# SM2200.net
KiCad netlist of a schematic drawn in Altium Designer
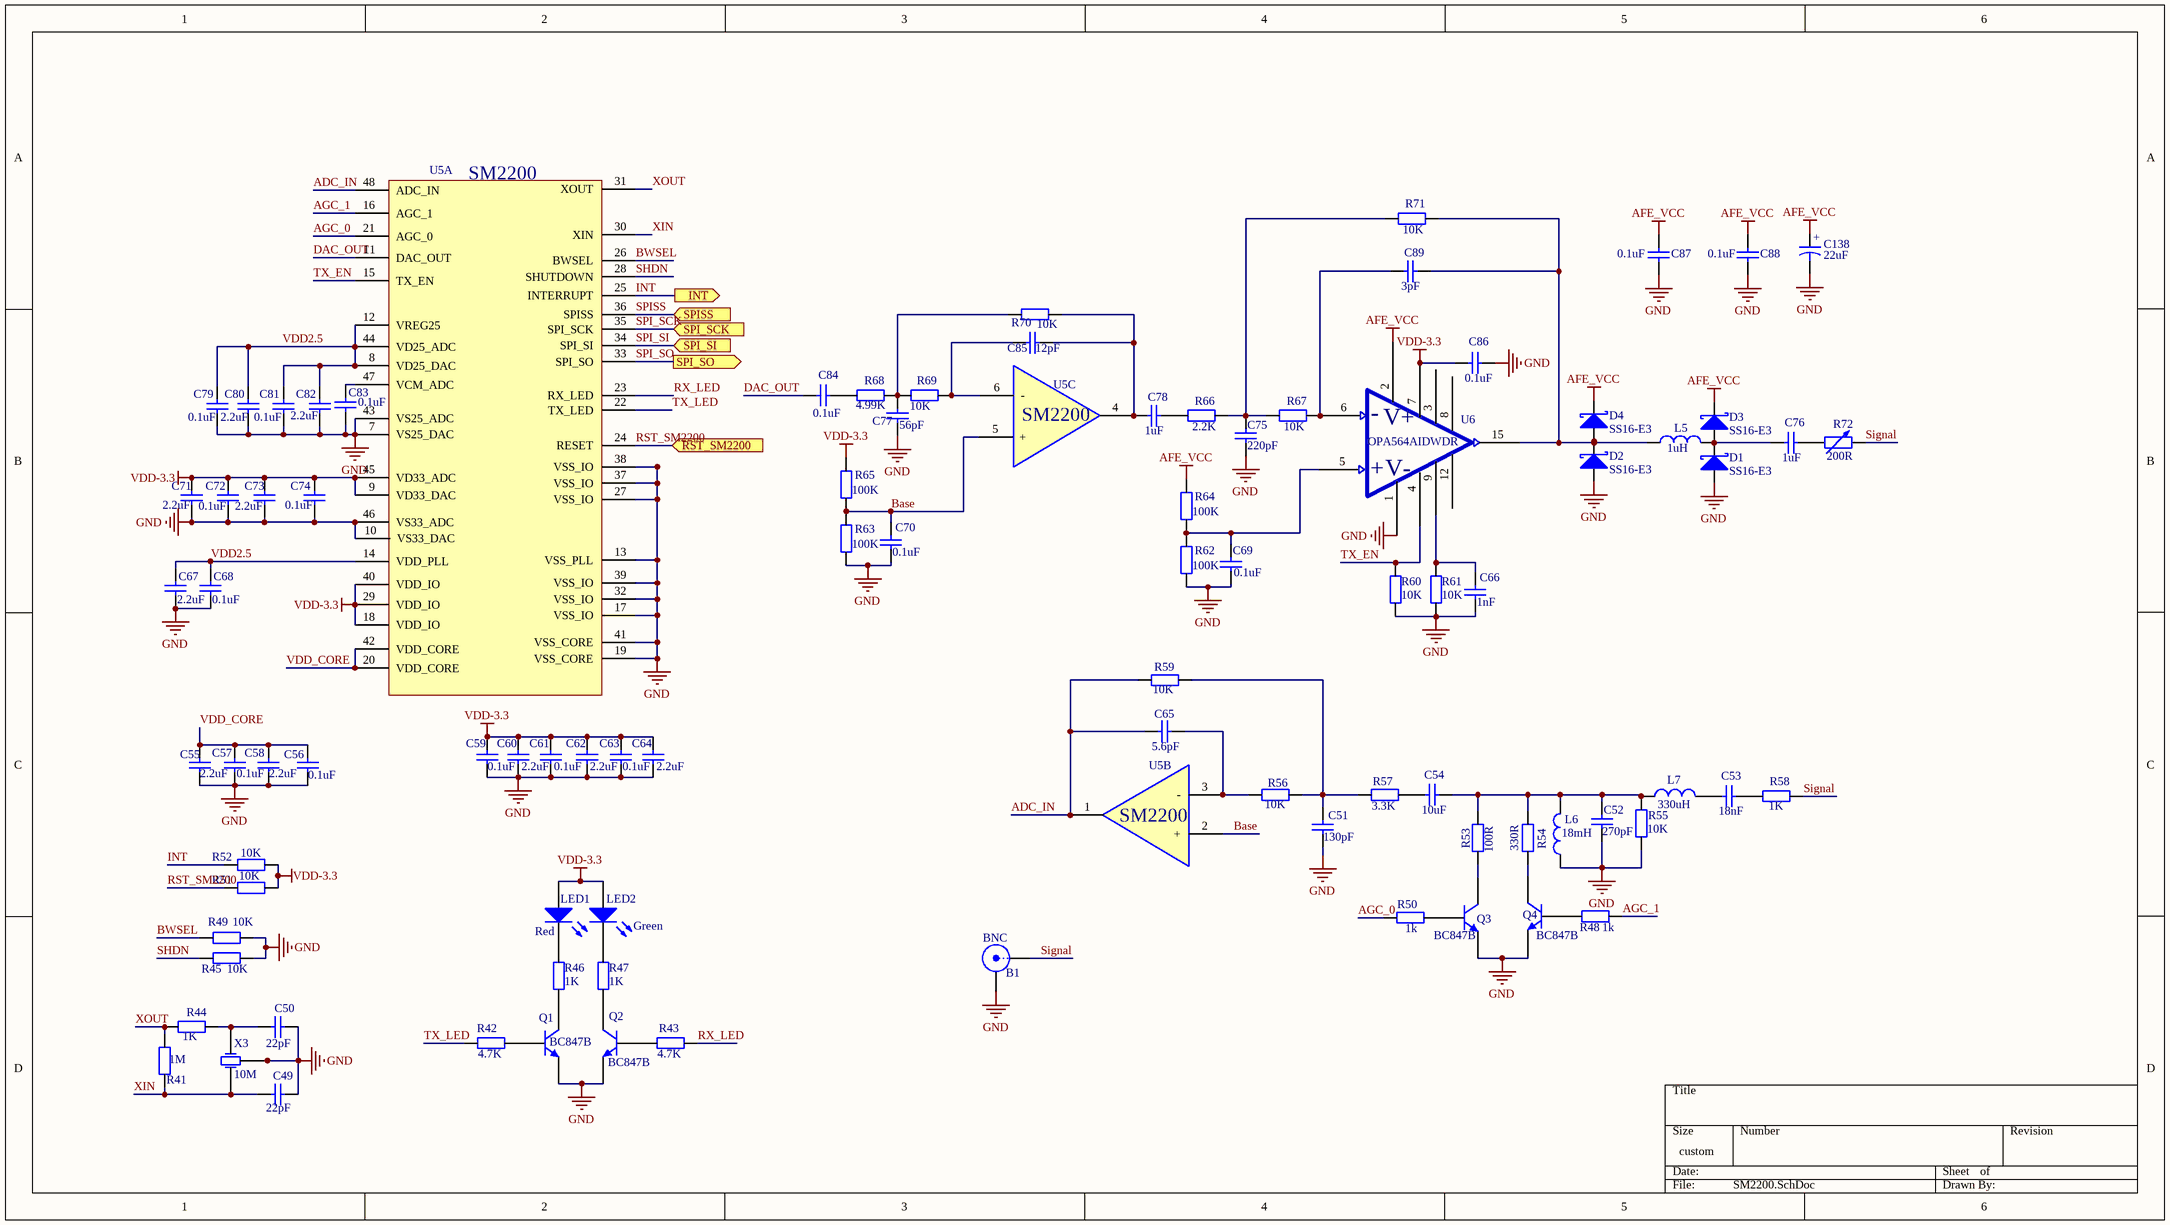
[diagram p0: SM2200.SchDoc]

(export (version "E")
  (design (tool "Eeschema 10.0.6"))
  (components
    (comp (ref "B1")
      (value "BNC")
      (footprint "BNC")
      (fields (field (name "NAME") "BNC"))
      (libsource (lib "原理图库") (part "BNC"))
    )
    (comp (ref "C49")
      (value "22pF")
      (footprint "0603")
      (fields (field (name "Comment") "Capacitor-0805"))
      (libsource (lib "原理图库") (part "Capacitor-0805"))
    )
    (comp (ref "C50")
      (value "22pF")
      (footprint "0603")
      (fields (field (name "Comment") "Capacitor-0805"))
      (libsource (lib "原理图库") (part "Capacitor-0805"))
    )
    (comp (ref "C51")
      (value "130pF")
      (footprint "0603")
      (fields (field (name "Comment") "Capacitor-0603"))
      (libsource (lib "原理图库") (part "Capacitor-0603"))
    )
    (comp (ref "C52")
      (value "270pF")
      (footprint "0603")
      (fields (field (name "Comment") "Capacitor-0603"))
      (libsource (lib "原理图库") (part "Capacitor-0603"))
    )
    (comp (ref "C53")
      (value "18nF")
      (footprint "0603")
      (fields (field (name "Comment") "Capacitor-0603"))
      (libsource (lib "原理图库") (part "Capacitor-0603"))
    )
    (comp (ref "C54")
      (value "10uF")
      (footprint "0805")
      (fields (field (name "Comment") "Capacitor-0603"))
      (libsource (lib "原理图库") (part "Capacitor-0603"))
    )
    (comp (ref "C55")
      (value "2.2uF")
      (footprint "0603")
      (fields (field (name "Comment") "Capacitor-0805"))
      (libsource (lib "原理图库") (part "Capacitor-0805"))
    )
    (comp (ref "C56")
      (value "0.1uF")
      (footprint "0603")
      (fields (field (name "Comment") "Capacitor-0805"))
      (libsource (lib "原理图库") (part "Capacitor-0805"))
    )
    (comp (ref "C57")
      (value "0.1uF")
      (footprint "0603")
      (fields (field (name "Comment") "Capacitor-0805"))
      (libsource (lib "原理图库") (part "Capacitor-0805"))
    )
    (comp (ref "C58")
      (value "2.2uF")
      (footprint "0603")
      (fields (field (name "Comment") "Capacitor-0805"))
      (libsource (lib "原理图库") (part "Capacitor-0805"))
    )
    (comp (ref "C59")
      (value "0.1uF")
      (footprint "0603")
      (fields (field (name "Comment") "Capacitor-0805"))
      (libsource (lib "原理图库") (part "Capacitor-0805"))
    )
    (comp (ref "C60")
      (value "2.2uF")
      (footprint "0603")
      (fields (field (name "Comment") "Capacitor-0805"))
      (libsource (lib "原理图库") (part "Capacitor-0805"))
    )
    (comp (ref "C61")
      (value "0.1uF")
      (footprint "0603")
      (fields (field (name "Comment") "Capacitor-0805"))
      (libsource (lib "原理图库") (part "Capacitor-0805"))
    )
    (comp (ref "C62")
      (value "2.2uF")
      (footprint "0603")
      (fields (field (name "Comment") "Capacitor-0805"))
      (libsource (lib "原理图库") (part "Capacitor-0805"))
    )
    (comp (ref "C63")
      (value "0.1uF")
      (footprint "0603")
      (fields (field (name "Comment") "Capacitor-0805"))
      (libsource (lib "原理图库") (part "Capacitor-0805"))
    )
    (comp (ref "C64")
      (value "2.2uF")
      (footprint "0603")
      (fields (field (name "Comment") "Capacitor-0805"))
      (libsource (lib "原理图库") (part "Capacitor-0805"))
    )
    (comp (ref "C65")
      (value "5.6pF")
      (footprint "0603")
      (fields (field (name "Comment") "Capacitor-0603"))
      (libsource (lib "原理图库") (part "Capacitor-0603"))
    )
    (comp (ref "C66")
      (value "1nF")
      (footprint "0603")
      (fields (field (name "Comment") "Capacitor-0603"))
      (libsource (lib "原理图库") (part "Capacitor-0603"))
    )
    (comp (ref "C67")
      (value "2.2uF")
      (footprint "0603")
      (fields (field (name "Comment") "Capacitor-0805"))
      (libsource (lib "原理图库") (part "Capacitor-0805"))
    )
    (comp (ref "C68")
      (value "0.1uF")
      (footprint "0603")
      (fields (field (name "Comment") "Capacitor-0805"))
      (libsource (lib "原理图库") (part "Capacitor-0805"))
    )
    (comp (ref "C69")
      (value "0.1uF")
      (footprint "0603")
      (fields (field (name "Comment") "Capacitor-0603"))
      (libsource (lib "原理图库") (part "Capacitor-0603"))
    )
    (comp (ref "C70")
      (value "0.1uF")
      (footprint "0603")
      (fields (field (name "Comment") "Capacitor-0603"))
      (libsource (lib "原理图库") (part "Capacitor-0603"))
    )
    (comp (ref "C71")
      (value "2.2uF")
      (footprint "0603")
      (fields (field (name "Comment") "Capacitor-0805"))
      (libsource (lib "原理图库") (part "Capacitor-0805"))
    )
    (comp (ref "C72")
      (value "0.1uF")
      (footprint "0603")
      (fields (field (name "Comment") "Capacitor-0805"))
      (libsource (lib "原理图库") (part "Capacitor-0805"))
    )
    (comp (ref "C73")
      (value "2.2uF")
      (footprint "0603")
      (fields (field (name "Comment") "Capacitor-0805"))
      (libsource (lib "原理图库") (part "Capacitor-0805"))
    )
    (comp (ref "C74")
      (value "0.1uF")
      (footprint "0603")
      (fields (field (name "Comment") "Capacitor-0805"))
      (libsource (lib "原理图库") (part "Capacitor-0805"))
    )
    (comp (ref "C75")
      (value "220pF")
      (footprint "0603")
      (fields (field (name "Comment") "Capacitor-0603"))
      (libsource (lib "原理图库") (part "Capacitor-0603"))
    )
    (comp (ref "C76")
      (value "1uF")
      (footprint "0603")
      (fields (field (name "Comment") "Capacitor-0603"))
      (libsource (lib "原理图库") (part "Capacitor-0603"))
    )
    (comp (ref "C77")
      (value "56pF")
      (footprint "0603")
      (fields (field (name "Comment") "Capacitor-0603"))
      (libsource (lib "原理图库") (part "Capacitor-0603"))
    )
    (comp (ref "C78")
      (value "1uF")
      (footprint "0603")
      (fields (field (name "Comment") "Capacitor-0603"))
      (libsource (lib "原理图库") (part "Capacitor-0603"))
    )
    (comp (ref "C79")
      (value "0.1uF")
      (footprint "0603")
      (fields (field (name "Comment") "Capacitor-0805"))
      (libsource (lib "原理图库") (part "Capacitor-0805"))
    )
    (comp (ref "C80")
      (value "2.2uF")
      (footprint "0603")
      (fields (field (name "Comment") "Capacitor-0805"))
      (libsource (lib "原理图库") (part "Capacitor-0805"))
    )
    (comp (ref "C81")
      (value "0.1uF")
      (footprint "0603")
      (fields (field (name "Comment") "Capacitor-0805"))
      (libsource (lib "原理图库") (part "Capacitor-0805"))
    )
    (comp (ref "C82")
      (value "2.2uF")
      (footprint "0603")
      (fields (field (name "Comment") "Capacitor-0805"))
      (libsource (lib "原理图库") (part "Capacitor-0805"))
    )
    (comp (ref "C83")
      (value "0.1uF")
      (footprint "0603")
      (fields (field (name "Comment") "Capacitor-0805"))
      (libsource (lib "原理图库") (part "Capacitor-0805"))
    )
    (comp (ref "C84")
      (value "0.1uF")
      (footprint "0603")
      (fields (field (name "Comment") "Capacitor-0603"))
      (libsource (lib "原理图库") (part "Capacitor-0603"))
    )
    (comp (ref "C85")
      (value "12pF")
      (footprint "0603")
      (fields (field (name "Comment") "Capacitor-0603"))
      (libsource (lib "原理图库") (part "Capacitor-0603"))
    )
    (comp (ref "C86")
      (value "0.1uF")
      (footprint "0603")
      (fields (field (name "Comment") "Capacitor-0603"))
      (libsource (lib "原理图库") (part "Capacitor-0603"))
    )
    (comp (ref "C87")
      (value "0.1uF")
      (footprint "0603")
      (fields (field (name "Comment") "Capacitor-0603"))
      (libsource (lib "原理图库") (part "Capacitor-0603"))
    )
    (comp (ref "C88")
      (value "0.1uF")
      (footprint "0603")
      (fields (field (name "Comment") "Capacitor-0603"))
      (libsource (lib "原理图库") (part "Capacitor-0603"))
    )
    (comp (ref "C89")
      (value "3pF")
      (footprint "0603")
      (fields (field (name "Comment") "Capacitor-0603"))
      (libsource (lib "原理图库") (part "Capacitor-0603"))
    )
    (comp (ref "C138")
      (value "22uF")
      (footprint "3528")
      (fields (field (name "ALTIUM_UNNAMED_1") "+") (field (name "Comment") "电解电容"))
      (libsource (lib "集成库—大岐") (part "电解电容"))
    )
    (comp (ref "D1")
      (value "SSA34")
      (footprint "IN5824")
      (fields (field (name "NAME") "SS16-E3"))
      (libsource (lib "原理图库") (part "SSA34"))
    )
    (comp (ref "D2")
      (value "SSA34")
      (footprint "IN5824")
      (fields (field (name "NAME") "SS16-E3"))
      (libsource (lib "原理图库") (part "SSA34"))
    )
    (comp (ref "D3")
      (value "SSA34")
      (footprint "IN5824")
      (fields (field (name "NAME") "SS16-E3"))
      (libsource (lib "原理图库") (part "SSA34"))
    )
    (comp (ref "D4")
      (value "SSA34")
      (footprint "IN5824")
      (fields (field (name "NAME") "SS16-E3"))
      (libsource (lib "原理图库") (part "SSA34"))
    )
    (comp (ref "L5")
      (value "1uH")
      (footprint "1206")
      (fields (field (name "Comment") "Inductor"))
      (libsource (lib "原理图库") (part "Inductor"))
    )
    (comp (ref "L6")
      (value "18mH")
      (footprint "工字电感0608")
      (fields (field (name "Comment") "Inductor"))
      (libsource (lib "原理图库") (part "Inductor"))
    )
    (comp (ref "L7")
      (value "330uH")
      (footprint "Inductor(7.8*7*5)")
      (fields (field (name "Comment") "Inductor"))
      (libsource (lib "原理图库") (part "Inductor"))
    )
    (comp (ref "LED1")
      (value "LED")
      (footprint "外插小灯")
      (fields (field (name "COLOR") "Red"))
      (libsource (lib "原理图库") (part "LED"))
    )
    (comp (ref "LED2")
      (value "LED")
      (footprint "外插小灯")
      (fields (field (name "COLOR") "Green"))
      (libsource (lib "原理图库") (part "LED"))
    )
    (comp (ref "Q1")
      (value "BC847")
      (footprint "BC847B")
      (fields (field (name "NAME") "BC847B"))
      (libsource (lib "原理图库") (part "BC847"))
    )
    (comp (ref "Q2")
      (value "BC847")
      (footprint "BC847B")
      (fields (field (name "NAME") "BC847B"))
      (libsource (lib "原理图库") (part "BC847"))
    )
    (comp (ref "Q3")
      (value "BC847")
      (footprint "BC847B")
      (fields (field (name "NAME") "BC847B"))
      (libsource (lib "原理图库") (part "BC847"))
    )
    (comp (ref "Q4")
      (value "BC847")
      (footprint "BC847B")
      (fields (field (name "NAME") "BC847B"))
      (libsource (lib "原理图库") (part "BC847"))
    )
    (comp (ref "R41")
      (value "1M")
      (footprint "0603")
      (fields (field (name "Comment") "Resistor-0805"))
      (libsource (lib "") (part "Resistor-0805_2"))
    )
    (comp (ref "R42")
      (value "4.7K")
      (footprint "0603")
      (fields (field (name "Comment") "Resistor-0805"))
      (libsource (lib "") (part "Resistor-0805_1"))
    )
    (comp (ref "R43")
      (value "4.7K")
      (footprint "0603")
      (fields (field (name "Comment") "Resistor-0805"))
      (libsource (lib "") (part "Resistor-0805_1"))
    )
    (comp (ref "R44")
      (value "1K")
      (footprint "0603")
      (fields (field (name "Comment") "Resistor-0805"))
      (libsource (lib "原理图库") (part "Resistor-0805"))
    )
    (comp (ref "R45")
      (value "10K")
      (footprint "0603")
      (fields (field (name "Comment") "Resistor-0805"))
      (libsource (lib "原理图库") (part "Resistor-0805"))
    )
    (comp (ref "R46")
      (value "1K")
      (footprint "0603")
      (fields (field (name "Comment") "Resistor-0805"))
      (libsource (lib "") (part "Resistor-0805_2"))
    )
    (comp (ref "R47")
      (value "1K")
      (footprint "0603")
      (fields (field (name "Comment") "Resistor-0805"))
      (libsource (lib "") (part "Resistor-0805_2"))
    )
    (comp (ref "R48")
      (value "1k")
      (footprint "0603")
      (fields (field (name "Comment") "Resistor-0603"))
      (libsource (lib "原理图库") (part "Resistor-0603"))
    )
    (comp (ref "R49")
      (value "10K")
      (footprint "0603")
      (fields (field (name "Comment") "Resistor-0805"))
      (libsource (lib "原理图库") (part "Resistor-0805"))
    )
    (comp (ref "R50")
      (value "1k")
      (footprint "0603")
      (fields (field (name "Comment") "Resistor-0603"))
      (libsource (lib "") (part "Resistor-0603_2"))
    )
    (comp (ref "R51")
      (value "10K")
      (footprint "0603")
      (fields (field (name "Comment") "Resistor-0805"))
      (libsource (lib "原理图库") (part "Resistor-0805"))
    )
    (comp (ref "R52")
      (value "10K")
      (footprint "0603")
      (fields (field (name "Comment") "Resistor-0805"))
      (libsource (lib "原理图库") (part "Resistor-0805"))
    )
    (comp (ref "R53")
      (value "100R")
      (footprint "0603")
      (fields (field (name "Comment") "Resistor-0603"))
      (libsource (lib "") (part "Resistor-0603_1"))
    )
    (comp (ref "R54")
      (value "330R")
      (footprint "0603")
      (fields (field (name "Comment") "Resistor-0603"))
      (libsource (lib "") (part "Resistor-0603_1"))
    )
    (comp (ref "R55")
      (value "10K")
      (footprint "0603")
      (fields (field (name "Comment") "Resistor-0603"))
      (libsource (lib "") (part "Resistor-0603_1"))
    )
    (comp (ref "R56")
      (value "10K")
      (footprint "0603")
      (fields (field (name "Comment") "Resistor-0603"))
      (libsource (lib "") (part "Resistor-0603_2"))
    )
    (comp (ref "R57")
      (value "3.3K")
      (footprint "0603")
      (fields (field (name "Comment") "Resistor-0603"))
      (libsource (lib "") (part "Resistor-0603_2"))
    )
    (comp (ref "R58")
      (value "1K")
      (footprint "0603")
      (fields (field (name "Comment") "Resistor-0603"))
      (libsource (lib "原理图库") (part "Resistor-0603"))
    )
    (comp (ref "R59")
      (value "10K")
      (footprint "0603")
      (fields (field (name "Comment") "Resistor-0603"))
      (libsource (lib "") (part "Resistor-0603_2"))
    )
    (comp (ref "R60")
      (value "10K")
      (footprint "0603")
      (fields (field (name "Comment") "Resistor-0603"))
      (libsource (lib "") (part "Resistor-0603_1"))
    )
    (comp (ref "R61")
      (value "10K")
      (footprint "0603")
      (fields (field (name "Comment") "Resistor-0603"))
      (libsource (lib "") (part "Resistor-0603_1"))
    )
    (comp (ref "R62")
      (value "100K")
      (footprint "0603")
      (fields (field (name "Comment") "Resistor-0603"))
      (libsource (lib "") (part "Resistor-0603_1"))
    )
    (comp (ref "R63")
      (value "100K")
      (footprint "0603")
      (fields (field (name "Comment") "Resistor-0603"))
      (libsource (lib "") (part "Resistor-0603_1"))
    )
    (comp (ref "R64")
      (value "100K")
      (footprint "0603")
      (fields (field (name "Comment") "Resistor-0603"))
      (libsource (lib "") (part "Resistor-0603_1"))
    )
    (comp (ref "R65")
      (value "100K")
      (footprint "0603")
      (fields (field (name "Comment") "Resistor-0603"))
      (libsource (lib "") (part "Resistor-0603_1"))
    )
    (comp (ref "R66")
      (value "2.2K")
      (footprint "0603")
      (fields (field (name "Comment") "Resistor-0603"))
      (libsource (lib "原理图库") (part "Resistor-0603"))
    )
    (comp (ref "R67")
      (value "10K")
      (footprint "0603")
      (fields (field (name "Comment") "Resistor-0603"))
      (libsource (lib "原理图库") (part "Resistor-0603"))
    )
    (comp (ref "R68")
      (value "4.99K")
      (footprint "0603")
      (fields (field (name "Comment") "Resistor-0603"))
      (libsource (lib "原理图库") (part "Resistor-0603"))
    )
    (comp (ref "R69")
      (value "10K")
      (footprint "0603")
      (fields (field (name "Comment") "Resistor-0603"))
      (libsource (lib "原理图库") (part "Resistor-0603"))
    )
    (comp (ref "R70")
      (value "10K")
      (footprint "0603")
      (fields (field (name "Comment") "Resistor-0603"))
      (libsource (lib "原理图库") (part "Resistor-0603"))
    )
    (comp (ref "R71")
      (value "10K")
      (footprint "0603")
      (fields (field (name "Comment") "Resistor-0603"))
      (libsource (lib "原理图库") (part "Resistor-0603"))
    )
    (comp (ref "R72")
      (value "200R")
      (footprint "3296电位器")
      (fields (field (name "Comment") "Res_"))
      (libsource (lib "原理图库") (part "Res_"))
    )
    (comp (ref "U5")
      (value "SM2200")
      (footprint "SM2200")
      (fields (field (name "ALTIUM_UNNAMED_1") "SM2200"))
      (libsource (lib "") (part "SM2200_1"))
    )
    (comp (ref "U6")
      (value "OPA564AIDWDR")
      (footprint "OPA564AIDWDR")
      (fields (field (name "NAME") "OPA564AIDWDR"))
      (libsource (lib "原理图库") (part "OPA564AIDWDR"))
    )
    (comp (ref "X3")
      (value "10M")
      (footprint "3225无源晶振")
      (fields (field (name "Comment") "3225无源晶振"))
      (libsource (lib "原理图库") (part "3225无源晶振"))
    )
  )
  (nets
    (net (code "1") (name "/ADC_IN") (class "Default")
      (node (ref "C65") (pin "1") (pinfunction "1_1") (pintype "passive"))
      (node (ref "R59") (pin "2") (pinfunction "2_2") (pintype "passive"))
      (node (ref "U5") (pin "1") (pintype "passive"))
      (node (ref "U5") (pin "48") (pinfunction "ADC_IN_48") (pintype "passive"))
    )
    (net (code "2") (name "/AGC_0") (class "Default")
      (node (ref "R50") (pin "2") (pinfunction "2_2") (pintype "passive"))
      (node (ref "U5") (pin "21") (pinfunction "AGC_0_21") (pintype "passive"))
    )
    (net (code "3") (name "/AGC_1") (class "Default")
      (node (ref "R48") (pin "2") (pinfunction "2_2") (pintype "passive"))
      (node (ref "U5") (pin "16") (pinfunction "AGC_1_16") (pintype "passive"))
    )
    (net (code "4") (name "/BWSEL") (class "Default")
      (node (ref "R49") (pin "1") (pinfunction "1_1") (pintype "passive"))
      (node (ref "U5") (pin "26") (pinfunction "BWSEL_26") (pintype "passive"))
    )
    (net (code "5") (name "/Base") (class "Default")
      (node (ref "C70") (pin "2") (pinfunction "2_2") (pintype "passive"))
      (node (ref "R63") (pin "2") (pinfunction "2_2") (pintype "passive"))
      (node (ref "R65") (pin "1") (pinfunction "1_1") (pintype "passive"))
      (node (ref "U5") (pin "2") (pinfunction "+_2") (pintype "passive"))
      (node (ref "U5") (pin "5") (pinfunction "+_5") (pintype "passive"))
    )
    (net (code "6") (name "/DAC_OUT") (class "Default")
      (node (ref "C84") (pin "2") (pinfunction "2_2") (pintype "passive"))
      (node (ref "U5") (pin "11") (pinfunction "DAC_OUT_11") (pintype "passive"))
    )
    (net (code "7") (name "/INT") (class "Default")
      (node (ref "R52") (pin "1") (pinfunction "1_1") (pintype "passive"))
      (node (ref "U5") (pin "25") (pinfunction "INTERRUPT_25") (pintype "passive"))
    )
    (net (code "8") (name "/RST_SM2200") (class "Default")
      (node (ref "R51") (pin "1") (pinfunction "1_1") (pintype "passive"))
      (node (ref "U5") (pin "24") (pinfunction "RESET_24") (pintype "passive"))
    )
    (net (code "9") (name "/RX_LED") (class "Default")
      (node (ref "R43") (pin "1") (pinfunction "1_1") (pintype "passive"))
      (node (ref "U5") (pin "23") (pinfunction "RX_LED_23") (pintype "passive"))
    )
    (net (code "10") (name "/SHDN") (class "Default")
      (node (ref "R45") (pin "1") (pinfunction "1_1") (pintype "passive"))
      (node (ref "U5") (pin "28") (pinfunction "SHUTDOWN_28") (pintype "passive"))
    )
    (net (code "11") (name "/SPISS") (class "Default")
      (node (ref "U5") (pin "36") (pinfunction "SPISS_36") (pintype "passive"))
    )
    (net (code "12") (name "/SPI_SCK") (class "Default")
      (node (ref "U5") (pin "35") (pinfunction "SPI_SCK_35") (pintype "passive"))
    )
    (net (code "13") (name "/SPI_SI") (class "Default")
      (node (ref "U5") (pin "34") (pinfunction "SPI_SI_34") (pintype "passive"))
    )
    (net (code "14") (name "/SPI_SO") (class "Default")
      (node (ref "U5") (pin "33") (pinfunction "SPI_SO_33") (pintype "passive"))
    )
    (net (code "15") (name "/Signal") (class "Default")
      (node (ref "B1") (pin "2") (pinfunction "X_2") (pintype "passive"))
      (node (ref "R58") (pin "2") (pinfunction "2_2") (pintype "passive"))
      (node (ref "R72") (pin "2") (pinfunction "2_2") (pintype "passive"))
    )
    (net (code "16") (name "/TX_EN") (class "Default")
      (node (ref "R60") (pin "2") (pinfunction "2_2") (pintype "passive"))
      (node (ref "U5") (pin "15") (pinfunction "TX_EN_15") (pintype "passive"))
      (node (ref "U6") (pin "4") (pintype "passive"))
    )
    (net (code "17") (name "/TX_LED") (class "Default")
      (node (ref "R42") (pin "2") (pinfunction "2_2") (pintype "passive"))
      (node (ref "U5") (pin "22") (pinfunction "TX_LED_22") (pintype "passive"))
    )
    (net (code "18") (name "/VDD2.5") (class "Default")
      (node (ref "C67") (pin "2") (pinfunction "2_2") (pintype "passive"))
      (node (ref "C68") (pin "2") (pinfunction "2_2") (pintype "passive"))
      (node (ref "C79") (pin "2") (pinfunction "2_2") (pintype "passive"))
      (node (ref "C80") (pin "2") (pinfunction "2_2") (pintype "passive"))
      (node (ref "C81") (pin "2") (pinfunction "2_2") (pintype "passive"))
      (node (ref "C82") (pin "2") (pinfunction "2_2") (pintype "passive"))
      (node (ref "U5") (pin "12") (pinfunction "VREG25_12") (pintype "passive"))
      (node (ref "U5") (pin "14") (pinfunction "VDD_PLL_14") (pintype "passive"))
      (node (ref "U5") (pin "44") (pinfunction "VD25_ADC_44") (pintype "passive"))
      (node (ref "U5") (pin "8") (pinfunction "VD25_DAC_8") (pintype "passive"))
    )
    (net (code "19") (name "/VDD_CORE") (class "Default")
      (node (ref "C55") (pin "2") (pinfunction "2_2") (pintype "passive"))
      (node (ref "C56") (pin "2") (pinfunction "2_2") (pintype "passive"))
      (node (ref "C57") (pin "2") (pinfunction "2_2") (pintype "passive"))
      (node (ref "C58") (pin "2") (pinfunction "2_2") (pintype "passive"))
      (node (ref "U5") (pin "20") (pinfunction "VDD_CORE_20") (pintype "passive"))
      (node (ref "U5") (pin "42") (pinfunction "VDD_CORE_42") (pintype "passive"))
    )
    (net (code "20") (name "/XIN") (class "Default")
      (node (ref "C49") (pin "1") (pinfunction "1_1") (pintype "passive"))
      (node (ref "R41") (pin "1") (pinfunction "1_1") (pintype "passive"))
      (node (ref "U5") (pin "30") (pinfunction "XIN_30") (pintype "passive"))
      (node (ref "X3") (pin "1") (pinfunction "OSC1_1") (pintype "passive"))
    )
    (net (code "21") (name "/XOUT") (class "Default")
      (node (ref "R41") (pin "2") (pinfunction "2_2") (pintype "passive"))
      (node (ref "R44") (pin "1") (pinfunction "1_1") (pintype "passive"))
      (node (ref "U5") (pin "31") (pinfunction "XOUT_31") (pintype "passive"))
    )
    (net (code "22") (name "AFE_VCC") (class "Default")
      (node (ref "C138") (pin "2") (pinfunction "2_2") (pintype "passive"))
      (node (ref "C87") (pin "2") (pinfunction "2_2") (pintype "passive"))
      (node (ref "C88") (pin "2") (pinfunction "2_2") (pintype "passive"))
      (node (ref "D3") (pin "2") (pinfunction "K_2") (pintype "passive"))
      (node (ref "D4") (pin "2") (pinfunction "K_2") (pintype "passive"))
      (node (ref "R64") (pin "2") (pinfunction "2_2") (pintype "passive"))
      (node (ref "U6") (pin "2") (pintype "passive"))
    )
    (net (code "23") (name "GND") (class "Default")
      (node (ref "B1") (pin "1") (pinfunction "Y_1") (pintype "passive"))
      (node (ref "C138") (pin "1") (pinfunction "1_1") (pintype "passive"))
      (node (ref "C49") (pin "2") (pinfunction "2_2") (pintype "passive"))
      (node (ref "C50") (pin "2") (pinfunction "2_2") (pintype "passive"))
      (node (ref "C51") (pin "2") (pinfunction "2_2") (pintype "passive"))
      (node (ref "C52") (pin "2") (pinfunction "2_2") (pintype "passive"))
      (node (ref "C55") (pin "1") (pinfunction "1_1") (pintype "passive"))
      (node (ref "C56") (pin "1") (pinfunction "1_1") (pintype "passive"))
      (node (ref "C57") (pin "1") (pinfunction "1_1") (pintype "passive"))
      (node (ref "C58") (pin "1") (pinfunction "1_1") (pintype "passive"))
      (node (ref "C59") (pin "1") (pinfunction "1_1") (pintype "passive"))
      (node (ref "C60") (pin "1") (pinfunction "1_1") (pintype "passive"))
      (node (ref "C61") (pin "1") (pinfunction "1_1") (pintype "passive"))
      (node (ref "C62") (pin "1") (pinfunction "1_1") (pintype "passive"))
      (node (ref "C63") (pin "1") (pinfunction "1_1") (pintype "passive"))
      (node (ref "C64") (pin "1") (pinfunction "1_1") (pintype "passive"))
      (node (ref "C66") (pin "1") (pinfunction "1_1") (pintype "passive"))
      (node (ref "C67") (pin "1") (pinfunction "1_1") (pintype "passive"))
      (node (ref "C68") (pin "1") (pinfunction "1_1") (pintype "passive"))
      (node (ref "C69") (pin "2") (pinfunction "2_2") (pintype "passive"))
      (node (ref "C70") (pin "1") (pinfunction "1_1") (pintype "passive"))
      (node (ref "C71") (pin "1") (pinfunction "1_1") (pintype "passive"))
      (node (ref "C72") (pin "1") (pinfunction "1_1") (pintype "passive"))
      (node (ref "C73") (pin "1") (pinfunction "1_1") (pintype "passive"))
      (node (ref "C74") (pin "1") (pinfunction "1_1") (pintype "passive"))
      (node (ref "C75") (pin "2") (pinfunction "2_2") (pintype "passive"))
      (node (ref "C77") (pin "1") (pinfunction "1_1") (pintype "passive"))
      (node (ref "C79") (pin "1") (pinfunction "1_1") (pintype "passive"))
      (node (ref "C80") (pin "1") (pinfunction "1_1") (pintype "passive"))
      (node (ref "C81") (pin "1") (pinfunction "1_1") (pintype "passive"))
      (node (ref "C82") (pin "1") (pinfunction "1_1") (pintype "passive"))
      (node (ref "C83") (pin "1") (pinfunction "1_1") (pintype "passive"))
      (node (ref "C86") (pin "1") (pinfunction "1_1") (pintype "passive"))
      (node (ref "C87") (pin "1") (pinfunction "1_1") (pintype "passive"))
      (node (ref "C88") (pin "1") (pinfunction "1_1") (pintype "passive"))
      (node (ref "D1") (pin "1") (pinfunction "A_1") (pintype "passive"))
      (node (ref "D2") (pin "1") (pinfunction "A_1") (pintype "passive"))
      (node (ref "L6") (pin "1") (pinfunction "1_1") (pintype "passive"))
      (node (ref "Q1") (pin "1") (pinfunction "E_1") (pintype "passive"))
      (node (ref "Q2") (pin "1") (pinfunction "E_1") (pintype "passive"))
      (node (ref "Q3") (pin "1") (pinfunction "E_1") (pintype "passive"))
      (node (ref "Q4") (pin "1") (pinfunction "E_1") (pintype "passive"))
      (node (ref "R45") (pin "2") (pinfunction "2_2") (pintype "passive"))
      (node (ref "R49") (pin "2") (pinfunction "2_2") (pintype "passive"))
      (node (ref "R55") (pin "1") (pinfunction "1_1") (pintype "passive"))
      (node (ref "R60") (pin "1") (pinfunction "1_1") (pintype "passive"))
      (node (ref "R61") (pin "1") (pinfunction "1_1") (pintype "passive"))
      (node (ref "R62") (pin "1") (pinfunction "1_1") (pintype "passive"))
      (node (ref "R63") (pin "1") (pinfunction "1_1") (pintype "passive"))
      (node (ref "U5") (pin "10") (pinfunction "VS33_DAC_10") (pintype "passive"))
      (node (ref "U5") (pin "13") (pinfunction "VSS_PLL_13") (pintype "passive"))
      (node (ref "U5") (pin "17") (pinfunction "VSS_IO_17") (pintype "passive"))
      (node (ref "U5") (pin "19") (pinfunction "VSS_CORE_19") (pintype "passive"))
      (node (ref "U5") (pin "27") (pinfunction "VSS_IO_27") (pintype "passive"))
      (node (ref "U5") (pin "32") (pinfunction "VSS_IO_32") (pintype "passive"))
      (node (ref "U5") (pin "37") (pinfunction "VSS_IO_37") (pintype "passive"))
      (node (ref "U5") (pin "38") (pinfunction "VSS_IO_38") (pintype "passive"))
      (node (ref "U5") (pin "39") (pinfunction "VSS_IO_39") (pintype "passive"))
      (node (ref "U5") (pin "41") (pinfunction "VSS_CORE_41") (pintype "passive"))
      (node (ref "U5") (pin "43") (pinfunction "VS25_ADC_43") (pintype "passive"))
      (node (ref "U5") (pin "46") (pinfunction "VS33_ADC_46") (pintype "passive"))
      (node (ref "U5") (pin "7") (pinfunction "VS25_DAC_7") (pintype "passive"))
      (node (ref "U6") (pin "1") (pintype "passive"))
      (node (ref "X3") (pin "2") (pinfunction "GND_2") (pintype "passive"))
      (node (ref "X3") (pin "4") (pinfunction "GND_4") (pintype "passive"))
    )
    (net (code "24") (name "Net-(C51-Pad1)") (class "Default")
      (node (ref "C51") (pin "1") (pinfunction "1_1") (pintype "passive"))
      (node (ref "R56") (pin "1") (pinfunction "1_1") (pintype "passive"))
      (node (ref "R57") (pin "2") (pinfunction "2_2") (pintype "passive"))
      (node (ref "R59") (pin "1") (pinfunction "1_1") (pintype "passive"))
    )
    (net (code "25") (name "Net-(C52-Pad1)") (class "Default")
      (node (ref "C52") (pin "1") (pinfunction "1_1") (pintype "passive"))
      (node (ref "C54") (pin "1") (pinfunction "1_1") (pintype "passive"))
      (node (ref "L6") (pin "2") (pinfunction "2_2") (pintype "passive"))
      (node (ref "L7") (pin "1") (pinfunction "1_1") (pintype "passive"))
      (node (ref "R53") (pin "2") (pinfunction "2_2") (pintype "passive"))
      (node (ref "R54") (pin "2") (pinfunction "2_2") (pintype "passive"))
      (node (ref "R55") (pin "2") (pinfunction "2_2") (pintype "passive"))
    )
    (net (code "26") (name "Net-(C53-Pad1)") (class "Default")
      (node (ref "C53") (pin "1") (pinfunction "1_1") (pintype "passive"))
      (node (ref "R58") (pin "1") (pinfunction "1_1") (pintype "passive"))
    )
    (net (code "27") (name "Net-(C53-Pad2)") (class "Default")
      (node (ref "C53") (pin "2") (pinfunction "2_2") (pintype "passive"))
      (node (ref "L7") (pin "2") (pinfunction "2_2") (pintype "passive"))
    )
    (net (code "28") (name "Net-(C54-Pad2)") (class "Default")
      (node (ref "C54") (pin "2") (pinfunction "2_2") (pintype "passive"))
      (node (ref "R57") (pin "1") (pinfunction "1_1") (pintype "passive"))
    )
    (net (code "29") (name "Net-(C66-Pad2)") (class "Default")
      (node (ref "C66") (pin "2") (pinfunction "2_2") (pintype "passive"))
      (node (ref "R61") (pin "2") (pinfunction "2_2") (pintype "passive"))
      (node (ref "U6") (pin "9") (pintype "passive"))
    )
    (net (code "30") (name "Net-(C75-Pad1)") (class "Default")
      (node (ref "C75") (pin "1") (pinfunction "1_1") (pintype "passive"))
      (node (ref "R66") (pin "2") (pinfunction "2_2") (pintype "passive"))
      (node (ref "R67") (pin "1") (pinfunction "1_1") (pintype "passive"))
      (node (ref "R71") (pin "1") (pinfunction "1_1") (pintype "passive"))
    )
    (net (code "31") (name "Net-(C76-Pad1)") (class "Default")
      (node (ref "C76") (pin "1") (pinfunction "1_1") (pintype "passive"))
      (node (ref "R72") (pin "1") (pinfunction "1_1") (pintype "passive"))
    )
    (net (code "32") (name "Net-(C77-Pad2)") (class "Default")
      (node (ref "C77") (pin "2") (pinfunction "2_2") (pintype "passive"))
      (node (ref "R68") (pin "2") (pinfunction "2_2") (pintype "passive"))
      (node (ref "R69") (pin "1") (pinfunction "1_1") (pintype "passive"))
      (node (ref "R70") (pin "1") (pinfunction "1_1") (pintype "passive"))
    )
    (net (code "33") (name "Net-(C78-Pad1)") (class "Default")
      (node (ref "C78") (pin "1") (pinfunction "1_1") (pintype "passive"))
      (node (ref "R66") (pin "1") (pinfunction "1_1") (pintype "passive"))
    )
    (net (code "34") (name "Net-(C78-Pad2)") (class "Default")
      (node (ref "C78") (pin "2") (pinfunction "2_2") (pintype "passive"))
      (node (ref "C85") (pin "1") (pinfunction "1_1") (pintype "passive"))
      (node (ref "R70") (pin "2") (pinfunction "2_2") (pintype "passive"))
      (node (ref "U5") (pin "4") (pintype "passive"))
    )
    (net (code "35") (name "Net-(C84-Pad1)") (class "Default")
      (node (ref "C84") (pin "1") (pinfunction "1_1") (pintype "passive"))
      (node (ref "R68") (pin "1") (pinfunction "1_1") (pintype "passive"))
    )
    (net (code "36") (name "Net-(D1-K)") (class "Default")
      (node (ref "C76") (pin "2") (pinfunction "2_2") (pintype "passive"))
      (node (ref "D1") (pin "2") (pinfunction "K_2") (pintype "passive"))
      (node (ref "D3") (pin "1") (pinfunction "A_1") (pintype "passive"))
      (node (ref "L5") (pin "2") (pinfunction "2_2") (pintype "passive"))
    )
    (net (code "37") (name "Net-(D2-K)") (class "Default")
      (node (ref "C89") (pin "1") (pinfunction "1_1") (pintype "passive"))
      (node (ref "D2") (pin "2") (pinfunction "K_2") (pintype "passive"))
      (node (ref "D4") (pin "1") (pinfunction "A_1") (pintype "passive"))
      (node (ref "L5") (pin "1") (pinfunction "1_1") (pintype "passive"))
      (node (ref "R71") (pin "2") (pinfunction "2_2") (pintype "passive"))
      (node (ref "U6") (pin "15") (pintype "passive"))
    )
    (net (code "38") (name "Net-(LED1-Pad2)") (class "Default")
      (node (ref "LED1") (pin "2") (pinfunction "2_2") (pintype "passive"))
      (node (ref "R46") (pin "2") (pinfunction "2_2") (pintype "passive"))
    )
    (net (code "39") (name "Net-(LED2-Pad2)") (class "Default")
      (node (ref "LED2") (pin "2") (pinfunction "2_2") (pintype "passive"))
      (node (ref "R47") (pin "2") (pinfunction "2_2") (pintype "passive"))
    )
    (net (code "40") (name "Net-(Q1-B)") (class "Default")
      (node (ref "Q1") (pin "2") (pinfunction "B_2") (pintype "passive"))
      (node (ref "R42") (pin "1") (pinfunction "1_1") (pintype "passive"))
    )
    (net (code "41") (name "Net-(Q1-C)") (class "Default")
      (node (ref "Q1") (pin "3") (pinfunction "C_3") (pintype "passive"))
      (node (ref "R46") (pin "1") (pinfunction "1_1") (pintype "passive"))
    )
    (net (code "42") (name "Net-(Q2-B)") (class "Default")
      (node (ref "Q2") (pin "2") (pinfunction "B_2") (pintype "passive"))
      (node (ref "R43") (pin "2") (pinfunction "2_2") (pintype "passive"))
    )
    (net (code "43") (name "Net-(Q2-C)") (class "Default")
      (node (ref "Q2") (pin "3") (pinfunction "C_3") (pintype "passive"))
      (node (ref "R47") (pin "1") (pinfunction "1_1") (pintype "passive"))
    )
    (net (code "44") (name "Net-(Q3-B)") (class "Default")
      (node (ref "Q3") (pin "2") (pinfunction "B_2") (pintype "passive"))
      (node (ref "R50") (pin "1") (pinfunction "1_1") (pintype "passive"))
    )
    (net (code "45") (name "Net-(Q3-C)") (class "Default")
      (node (ref "Q3") (pin "3") (pinfunction "C_3") (pintype "passive"))
      (node (ref "R53") (pin "1") (pinfunction "1_1") (pintype "passive"))
    )
    (net (code "46") (name "Net-(Q4-B)") (class "Default")
      (node (ref "Q4") (pin "2") (pinfunction "B_2") (pintype "passive"))
      (node (ref "R48") (pin "1") (pinfunction "1_1") (pintype "passive"))
    )
    (net (code "47") (name "Net-(Q4-C)") (class "Default")
      (node (ref "Q4") (pin "3") (pinfunction "C_3") (pintype "passive"))
      (node (ref "R54") (pin "1") (pinfunction "1_1") (pintype "passive"))
    )
    (net (code "48") (name "Net-(U5A-VCM_ADC)") (class "Default")
      (node (ref "C83") (pin "2") (pinfunction "2_2") (pintype "passive"))
      (node (ref "U5") (pin "47") (pinfunction "VCM_ADC_47") (pintype "passive"))
    )
    (net (code "49") (name "Net-(U5B--)") (class "Default")
      (node (ref "C65") (pin "2") (pinfunction "2_2") (pintype "passive"))
      (node (ref "R56") (pin "2") (pinfunction "2_2") (pintype "passive"))
      (node (ref "U5") (pin "3") (pinfunction "-_3") (pintype "passive"))
    )
    (net (code "50") (name "Net-(U5C--)") (class "Default")
      (node (ref "C85") (pin "2") (pinfunction "2_2") (pintype "passive"))
      (node (ref "R69") (pin "2") (pinfunction "2_2") (pintype "passive"))
      (node (ref "U5") (pin "6") (pinfunction "-_6") (pintype "passive"))
    )
    (net (code "51") (name "Net-(U6-9)") (class "Default")
      (node (ref "C89") (pin "2") (pinfunction "2_2") (pintype "passive"))
      (node (ref "R67") (pin "2") (pinfunction "2_2") (pintype "passive"))
      (node (ref "U6") (pin "6") (pinfunction "9_6") (pintype "passive"))
    )
    (net (code "52") (name "Net-(U6-10)") (class "Default")
      (node (ref "C69") (pin "1") (pinfunction "1_1") (pintype "passive"))
      (node (ref "R62") (pin "2") (pinfunction "2_2") (pintype "passive"))
      (node (ref "R64") (pin "1") (pinfunction "1_1") (pintype "passive"))
      (node (ref "U6") (pin "5") (pinfunction "10_5") (pintype "passive"))
    )
    (net (code "53") (name "Net-(X3-OSC2)") (class "Default")
      (node (ref "C50") (pin "1") (pinfunction "1_1") (pintype "passive"))
      (node (ref "R44") (pin "2") (pinfunction "2_2") (pintype "passive"))
      (node (ref "X3") (pin "3") (pinfunction "OSC2_3") (pintype "passive"))
    )
    (net (code "54") (name "VDD-3.3") (class "Default")
      (node (ref "C59") (pin "2") (pinfunction "2_2") (pintype "passive"))
      (node (ref "C60") (pin "2") (pinfunction "2_2") (pintype "passive"))
      (node (ref "C61") (pin "2") (pinfunction "2_2") (pintype "passive"))
      (node (ref "C62") (pin "2") (pinfunction "2_2") (pintype "passive"))
      (node (ref "C63") (pin "2") (pinfunction "2_2") (pintype "passive"))
      (node (ref "C64") (pin "2") (pinfunction "2_2") (pintype "passive"))
      (node (ref "C71") (pin "2") (pinfunction "2_2") (pintype "passive"))
      (node (ref "C72") (pin "2") (pinfunction "2_2") (pintype "passive"))
      (node (ref "C73") (pin "2") (pinfunction "2_2") (pintype "passive"))
      (node (ref "C74") (pin "2") (pinfunction "2_2") (pintype "passive"))
      (node (ref "C86") (pin "2") (pinfunction "2_2") (pintype "passive"))
      (node (ref "LED1") (pin "1") (pinfunction "A_1") (pintype "passive"))
      (node (ref "LED2") (pin "1") (pinfunction "A_1") (pintype "passive"))
      (node (ref "R51") (pin "2") (pinfunction "2_2") (pintype "passive"))
      (node (ref "R52") (pin "2") (pinfunction "2_2") (pintype "passive"))
      (node (ref "R65") (pin "2") (pinfunction "2_2") (pintype "passive"))
      (node (ref "U5") (pin "18") (pinfunction "VDD_IO_18") (pintype "passive"))
      (node (ref "U5") (pin "29") (pinfunction "VDD_IO_29") (pintype "passive"))
      (node (ref "U5") (pin "40") (pinfunction "VDD_IO_40") (pintype "passive"))
      (node (ref "U5") (pin "45") (pinfunction "VD33_ADC_45") (pintype "passive"))
      (node (ref "U5") (pin "9") (pinfunction "VD33_DAC_9") (pintype "passive"))
      (node (ref "U6") (pin "7") (pintype "passive"))
    )
    (net (code "55") (name "unconnected-(U6-Pad3)") (class "Default")
      (node (ref "U6") (pin "3") (pintype "passive"))
    )
    (net (code "56") (name "unconnected-(U6-Pad8)") (class "Default")
      (node (ref "U6") (pin "8") (pintype "passive"))
    )
    (net (code "57") (name "unconnected-(U6-Pad12)") (class "Default")
      (node (ref "U6") (pin "12") (pintype "passive"))
    )
  )
)
